# Timer.net
KiCad netlist of a schematic drawn in Altium Designer
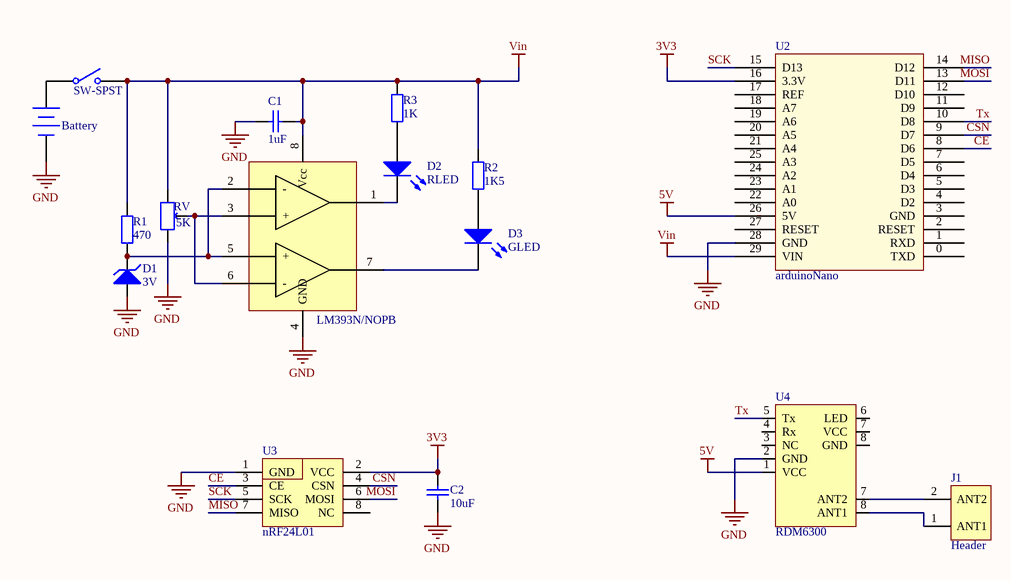
[diagram p0: Timer.SchDoc]

(export (version "E")
  (design (tool "Eeschema 10.0.6"))
  (components
    (comp (ref "BT1")
      (value "Battery")
      (footprint "BAT-2")
      (description "Multicell Battery")
      (fields (field (name "PUBLISHER") "Altium Limited"))
      (libsource (lib "Miscellaneous Devices") (part "Battery"))
    )
    (comp (ref "C1")
      (value "1uF")
      (footprint "RAD-0.3")
      (description "Capacitor")
      (fields (field (name "PUBLISHER") "Altium Limited"))
      (libsource (lib "Miscellaneous Devices") (part "Cap"))
    )
    (comp (ref "C2")
      (value "10uF")
      (footprint "RAD-0.3")
      (description "Capacitor")
      (fields (field (name "PUBLISHER") "Altium Limited"))
      (libsource (lib "Miscellaneous Devices") (part "Cap"))
    )
    (comp (ref "D1")
      (value "3V")
      (description "DIODE ZENER 3V 500MW DO-35")
      (fields
        (field (name "MANUFACTURER") "NXP Semiconductors")
        (field (name "MANUFACTURER PART NUMBER") "BZX79-C3V0,113")
      )
      (libsource (lib "skeemitehnika_lib") (part "BZX79-C3V0,113"))
    )
    (comp (ref "D2")
      (value "RLED")
      (footprint "LED-0")
      (description "Typical INFRARED GaAs LED")
      (fields (field (name "PUBLISHER") "Altium Limited"))
      (libsource (lib "Miscellaneous Devices") (part "LED0"))
    )
    (comp (ref "D3")
      (value "GLED")
      (footprint "LED-0")
      (description "Typical INFRARED GaAs LED")
      (fields (field (name "PUBLISHER") "Altium Limited"))
      (libsource (lib "skeemitehnika_lib") (part "LED0"))
    )
    (comp (ref "J1") (value "Header") (libsource (lib "skeemitehnika_lib") (part "Antenna header")))
    (comp (ref "R1")
      (value "470")
      (footprint "AXIAL-0.4")
      (description "Resistor")
      (fields (field (name "PUBLISHER") "Altium Limited"))
      (libsource (lib "Miscellaneous Devices") (part "Res2"))
    )
    (comp (ref "R2")
      (value "1K5")
      (footprint "AXIAL-0.4")
      (description "Resistor")
      (fields (field (name "PUBLISHER") "Altium Limited"))
      (libsource (lib "Miscellaneous Devices") (part "Res2"))
    )
    (comp (ref "R3")
      (value "1K")
      (footprint "AXIAL-0.4")
      (description "Resistor")
      (fields (field (name "PUBLISHER") "Altium Limited"))
      (libsource (lib "Miscellaneous Devices") (part "Res2"))
    )
    (comp (ref "RV") (value "5K") (libsource (lib "skeemitehnika_lib") (part "Trimmer")))
    (comp (ref "S1")
      (value "SW-SPST")
      (footprint "SPST-2")
      (description "Single-Pole, Single-Throw Switch")
      (fields (field (name "PUBLISHER") "Altium Limited"))
      (libsource (lib "Miscellaneous Devices") (part "SW-SPST"))
    )
    (comp (ref "U1")
      (value "LM393N/NOPB")
      (fields (field (name "MANUFACTURER") "TI National Semiconductor"))
      (libsource (lib "skeemitehnika_lib") (part "LM393N/NOPB"))
    )
    (comp (ref "U2")
      (value "arduinoNano")
      (footprint "Arduino nano")
      (libsource (lib "skeemitehnika_lib") (part "arduinoNano"))
    )
    (comp (ref "U3") (value "nRF24L01") (libsource (lib "skeemitehnika_lib") (part "nRF24L01")))
    (comp (ref "U4") (value "RDM6300") (libsource (lib "skeemitehnika_lib") (part "RDM6300")))
  )
  (nets
    (net (code "1") (name "/CE") (class "Default")
      (node (ref "U2") (pin "8") (pinfunction "D6_8") (pintype "passive"))
      (node (ref "U3") (pin "3") (pinfunction "CE_3") (pintype "passive"))
    )
    (net (code "2") (name "/CSN") (class "Default")
      (node (ref "U2") (pin "9") (pinfunction "D7_9") (pintype "passive"))
      (node (ref "U3") (pin "4") (pinfunction "CSN_4") (pintype "passive"))
    )
    (net (code "3") (name "/MISO") (class "Default")
      (node (ref "U2") (pin "14") (pinfunction "D12_14") (pintype "passive"))
      (node (ref "U3") (pin "7") (pinfunction "MISO_7") (pintype "passive"))
    )
    (net (code "4") (name "/MOSI") (class "Default")
      (node (ref "U2") (pin "13") (pinfunction "D11_13") (pintype "passive"))
      (node (ref "U3") (pin "6") (pinfunction "MOSI_6") (pintype "passive"))
    )
    (net (code "5") (name "/SCK") (class "Default")
      (node (ref "U2") (pin "15") (pinfunction "D13_15") (pintype "passive"))
      (node (ref "U3") (pin "5") (pinfunction "SCK_5") (pintype "passive"))
    )
    (net (code "6") (name "/Tx") (class "Default")
      (node (ref "U2") (pin "10") (pinfunction "D8_10") (pintype "passive"))
      (node (ref "U4") (pin "5") (pinfunction "Tx_5") (pintype "passive"))
    )
    (net (code "7") (name "3V3") (class "Default")
      (node (ref "C2") (pin "1") (pinfunction "1_1") (pintype "passive"))
      (node (ref "U2") (pin "16") (pinfunction "3.3V_16") (pintype "passive"))
      (node (ref "U3") (pin "2") (pinfunction "VCC_2") (pintype "passive"))
    )
    (net (code "8") (name "5V") (class "Default")
      (node (ref "U2") (pin "26") (pinfunction "5V_26") (pintype "passive"))
      (node (ref "U4") (pin "1") (pinfunction "VCC_1") (pintype "passive"))
    )
    (net (code "9") (name "GND") (class "Default")
      (node (ref "BT1") (pin "2") (pinfunction "-_2") (pintype "passive"))
      (node (ref "C1") (pin "2") (pinfunction "2_2") (pintype "passive"))
      (node (ref "C2") (pin "2") (pinfunction "2_2") (pintype "passive"))
      (node (ref "D1") (pin "2") (pinfunction "2_2") (pintype "passive"))
      (node (ref "RV") (pin "1") (pinfunction "1_1") (pintype "passive"))
      (node (ref "U1") (pin "4") (pinfunction "GND_4") (pintype "passive"))
      (node (ref "U2") (pin "28") (pinfunction "GND_28") (pintype "passive"))
      (node (ref "U3") (pin "1") (pinfunction "GND_1") (pintype "passive"))
      (node (ref "U4") (pin "2") (pinfunction "GND_2") (pintype "passive"))
    )
    (net (code "10") (name "Net-(BT1-+)") (class "Default")
      (node (ref "BT1") (pin "1") (pinfunction "+_1") (pintype "passive"))
      (node (ref "S1") (pin "1") (pinfunction "COMMON_1") (pintype "passive"))
    )
    (net (code "11") (name "Net-(D1-Pad1)") (class "Default")
      (node (ref "D1") (pin "1") (pinfunction "1_1") (pintype "passive"))
      (node (ref "R1") (pin "1") (pinfunction "1_1") (pintype "passive"))
      (node (ref "U1") (pin "2") (pinfunction "-_2") (pintype "passive"))
      (node (ref "U1") (pin "5") (pinfunction "+_5") (pintype "passive"))
    )
    (net (code "12") (name "Net-(D2-A)") (class "Default")
      (node (ref "D2") (pin "1") (pinfunction "A_1") (pintype "passive"))
      (node (ref "R3") (pin "1") (pinfunction "1_1") (pintype "passive"))
    )
    (net (code "13") (name "Net-(D2-K)") (class "Default")
      (node (ref "D2") (pin "2") (pinfunction "K_2") (pintype "passive"))
      (node (ref "U1") (pin "1") (pinfunction "Aout_1") (pintype "passive"))
    )
    (net (code "14") (name "Net-(D3-A)") (class "Default")
      (node (ref "D3") (pin "1") (pinfunction "A_1") (pintype "passive"))
      (node (ref "R2") (pin "1") (pinfunction "1_1") (pintype "passive"))
    )
    (net (code "15") (name "Net-(D3-K)") (class "Default")
      (node (ref "D3") (pin "2") (pinfunction "K_2") (pintype "passive"))
      (node (ref "U1") (pin "7") (pinfunction "Bout_7") (pintype "passive"))
    )
    (net (code "16") (name "Net-(J1-ANT1)") (class "Default")
      (node (ref "J1") (pin "1") (pinfunction "ANT1_1") (pintype "passive"))
      (node (ref "U4") (pin "8") (pinfunction "ANT1_8") (pintype "passive"))
    )
    (net (code "17") (name "Net-(J1-ANT2)") (class "Default")
      (node (ref "J1") (pin "2") (pinfunction "ANT2_2") (pintype "passive"))
      (node (ref "U4") (pin "7") (pinfunction "ANT2_7") (pintype "passive"))
    )
    (net (code "18") (name "Net-(RV-Pad2)") (class "Default")
      (node (ref "RV") (pin "2") (pinfunction "2_2") (pintype "passive"))
      (node (ref "U1") (pin "3") (pinfunction "+_3") (pintype "passive"))
      (node (ref "U1") (pin "6") (pinfunction "-_6") (pintype "passive"))
    )
    (net (code "19") (name "Vin") (class "Default")
      (node (ref "C1") (pin "1") (pinfunction "1_1") (pintype "passive"))
      (node (ref "R1") (pin "2") (pinfunction "2_2") (pintype "passive"))
      (node (ref "R2") (pin "2") (pinfunction "2_2") (pintype "passive"))
      (node (ref "R3") (pin "2") (pinfunction "2_2") (pintype "passive"))
      (node (ref "RV") (pin "3") (pinfunction "3_3") (pintype "passive"))
      (node (ref "S1") (pin "2") (pinfunction "NO_2") (pintype "passive"))
      (node (ref "U1") (pin "8") (pinfunction "Vcc_8") (pintype "passive"))
      (node (ref "U2") (pin "29") (pinfunction "VIN_29") (pintype "passive"))
    )
    (net (code "20") (name "unconnected-(U2-A0-Pad22)") (class "Default")
      (node (ref "U2") (pin "22") (pinfunction "A0_22") (pintype "passive"))
    )
    (net (code "21") (name "unconnected-(U2-A1-Pad23)") (class "Default")
      (node (ref "U2") (pin "23") (pinfunction "A1_23") (pintype "passive"))
    )
    (net (code "22") (name "unconnected-(U2-A2-Pad24)") (class "Default")
      (node (ref "U2") (pin "24") (pinfunction "A2_24") (pintype "passive"))
    )
    (net (code "23") (name "unconnected-(U2-A3-Pad25)") (class "Default")
      (node (ref "U2") (pin "25") (pinfunction "A3_25") (pintype "passive"))
    )
    (net (code "24") (name "unconnected-(U2-A4-Pad21)") (class "Default")
      (node (ref "U2") (pin "21") (pinfunction "A4_21") (pintype "passive"))
    )
    (net (code "25") (name "unconnected-(U2-A5-Pad20)") (class "Default")
      (node (ref "U2") (pin "20") (pinfunction "A5_20") (pintype "passive"))
    )
    (net (code "26") (name "unconnected-(U2-A6-Pad19)") (class "Default")
      (node (ref "U2") (pin "19") (pinfunction "A6_19") (pintype "passive"))
    )
    (net (code "27") (name "unconnected-(U2-A7-Pad18)") (class "Default")
      (node (ref "U2") (pin "18") (pinfunction "A7_18") (pintype "passive"))
    )
    (net (code "28") (name "unconnected-(U2-D2-Pad4)") (class "Default")
      (node (ref "U2") (pin "4") (pinfunction "D2_4") (pintype "passive"))
    )
    (net (code "29") (name "unconnected-(U2-D3-Pad5)") (class "Default")
      (node (ref "U2") (pin "5") (pinfunction "D3_5") (pintype "passive"))
    )
    (net (code "30") (name "unconnected-(U2-D4-Pad6)") (class "Default")
      (node (ref "U2") (pin "6") (pinfunction "D4_6") (pintype "passive"))
    )
    (net (code "31") (name "unconnected-(U2-D5-Pad7)") (class "Default")
      (node (ref "U2") (pin "7") (pinfunction "D5_7") (pintype "passive"))
    )
    (net (code "32") (name "unconnected-(U2-D9-Pad11)") (class "Default")
      (node (ref "U2") (pin "11") (pinfunction "D9_11") (pintype "passive"))
    )
    (net (code "33") (name "unconnected-(U2-D10-Pad12)") (class "Default")
      (node (ref "U2") (pin "12") (pinfunction "D10_12") (pintype "passive"))
    )
    (net (code "34") (name "unconnected-(U2-GND-Pad3)") (class "Default")
      (node (ref "U2") (pin "3") (pinfunction "GND_3") (pintype "passive"))
    )
    (net (code "35") (name "unconnected-(U2-REF-Pad17)") (class "Default")
      (node (ref "U2") (pin "17") (pinfunction "REF_17") (pintype "passive"))
    )
    (net (code "36") (name "unconnected-(U2-RESET-Pad2)") (class "Default")
      (node (ref "U2") (pin "2") (pinfunction "RESET_2") (pintype "passive"))
    )
    (net (code "37") (name "unconnected-(U2-RESET-Pad27)") (class "Default")
      (node (ref "U2") (pin "27") (pinfunction "RESET_27") (pintype "passive"))
    )
    (net (code "38") (name "unconnected-(U2-RXD-Pad1)") (class "Default")
      (node (ref "U2") (pin "1") (pinfunction "RXD_1") (pintype "passive"))
    )
    (net (code "39") (name "unconnected-(U2-TXD-Pad0)") (class "Default")
      (node (ref "U2") (pin "0") (pinfunction "TXD_0") (pintype "passive"))
    )
    (net (code "40") (name "unconnected-(U3-NC-Pad8)") (class "Default")
      (node (ref "U3") (pin "8") (pinfunction "NC_8") (pintype "passive"))
    )
    (net (code "41") (name "unconnected-(U4-GND-Pad8)") (class "Default")
      (node (ref "U4") (pin "8") (pinfunction "GND_8") (pintype "passive"))
    )
    (net (code "42") (name "unconnected-(U4-LED-Pad6)") (class "Default")
      (node (ref "U4") (pin "6") (pinfunction "LED_6") (pintype "passive"))
    )
    (net (code "43") (name "unconnected-(U4-NC-Pad3)") (class "Default")
      (node (ref "U4") (pin "3") (pinfunction "NC_3") (pintype "passive"))
    )
    (net (code "44") (name "unconnected-(U4-Rx-Pad4)") (class "Default")
      (node (ref "U4") (pin "4") (pinfunction "Rx_4") (pintype "passive"))
    )
    (net (code "45") (name "unconnected-(U4-VCC-Pad7)") (class "Default")
      (node (ref "U4") (pin "7") (pinfunction "VCC_7") (pintype "passive"))
    )
  )
)
